# P_ytka_ESPv1.net
KiCad netlist of a schematic drawn in EAGLE
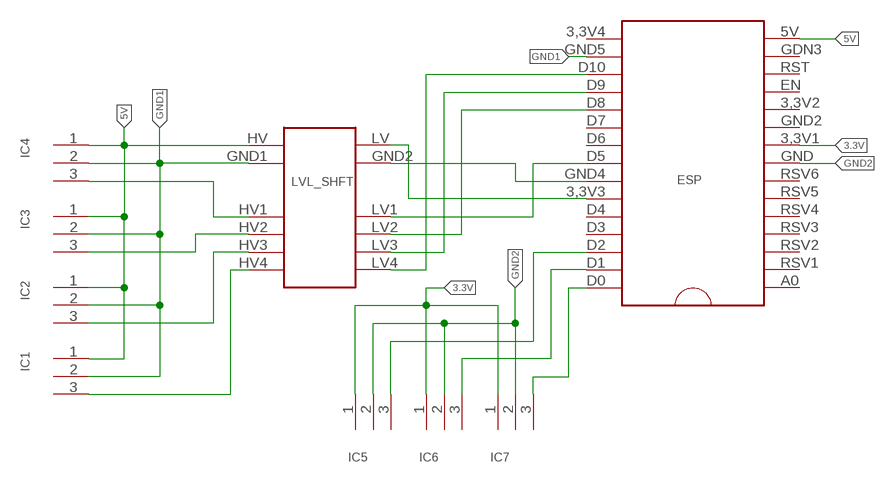
[diagram p0: schematic, sheet 1]

(export (version "E")
  (design (tool "Eeschema 10.0.6"))
  (components
    (comp (ref "ESP")
      (value "ESP8266_NODEMCUV2")
      (footprint "eagle-import:ESP8266_NODEMCV2")
      (libsource (lib "eagle-import") (part "ESP8266_NODEMCUV2"))
    )
    (comp (ref "IC1")
      (value "3,5MM_3PIN")
      (footprint "eagle-import:3,5MM_3PIN")
      (libsource (lib "eagle-import") (part "3,5MM_3PIN"))
    )
    (comp (ref "IC2")
      (value "3,5MM_3PIN")
      (footprint "eagle-import:3,5MM_3PIN")
      (libsource (lib "eagle-import") (part "3,5MM_3PIN"))
    )
    (comp (ref "IC3")
      (value "3,5MM_3PIN")
      (footprint "eagle-import:3,5MM_3PIN")
      (libsource (lib "eagle-import") (part "3,5MM_3PIN"))
    )
    (comp (ref "IC4")
      (value "3,5MM_3PIN")
      (footprint "eagle-import:3,5MM_3PIN")
      (libsource (lib "eagle-import") (part "3,5MM_3PIN"))
    )
    (comp (ref "IC5")
      (value "3,5MM_3PIN")
      (footprint "eagle-import:3,5MM_3PIN")
      (libsource (lib "eagle-import") (part "3,5MM_3PIN"))
    )
    (comp (ref "IC6")
      (value "3,5MM_3PIN")
      (footprint "eagle-import:3,5MM_3PIN")
      (libsource (lib "eagle-import") (part "3,5MM_3PIN"))
    )
    (comp (ref "IC7")
      (value "3,5MM_3PIN")
      (footprint "eagle-import:3,5MM_3PIN")
      (libsource (lib "eagle-import") (part "3,5MM_3PIN"))
    )
    (comp (ref "LVL_SHFT")
      (value "LVL_SHIFTER_4CH")
      (footprint "eagle-import:LVL_SHIFTER_4CH")
      (libsource (lib "eagle-import") (part "LVL_SHIFTER_4CH"))
    )
  )
  (nets
    (net (code "1") (name "3.3V") (class "Default")
      (node (ref "ESP") (pin "3,3V1") (pinfunction "P$9_3,3V1") (pintype "bidirectional"))
      (node (ref "IC5") (pin "1") (pinfunction "P$1_1") (pintype "bidirectional"))
      (node (ref "IC6") (pin "1") (pinfunction "P$1_1") (pintype "bidirectional"))
      (node (ref "IC7") (pin "1") (pinfunction "P$1_1") (pintype "bidirectional"))
    )
    (net (code "2") (name "5V") (class "Default")
      (node (ref "ESP") (pin "5V") (pinfunction "P$15_5V") (pintype "bidirectional"))
      (node (ref "IC1") (pin "1") (pinfunction "P$1_1") (pintype "bidirectional"))
      (node (ref "IC2") (pin "1") (pinfunction "P$1_1") (pintype "bidirectional"))
      (node (ref "IC3") (pin "1") (pinfunction "P$1_1") (pintype "bidirectional"))
      (node (ref "IC4") (pin "1") (pinfunction "P$1_1") (pintype "bidirectional"))
      (node (ref "LVL_SHFT") (pin "HV") (pinfunction "HV_HV") (pintype "bidirectional"))
    )
    (net (code "3") (name "GND1") (class "Default")
      (node (ref "ESP") (pin "GND5") (pinfunction "P$17_GND5") (pintype "bidirectional"))
      (node (ref "IC1") (pin "2") (pinfunction "P$2_2") (pintype "bidirectional"))
      (node (ref "IC2") (pin "2") (pinfunction "P$2_2") (pintype "bidirectional"))
      (node (ref "IC3") (pin "2") (pinfunction "P$2_2") (pintype "bidirectional"))
      (node (ref "IC4") (pin "2") (pinfunction "P$2_2") (pintype "bidirectional"))
      (node (ref "LVL_SHFT") (pin "GND1") (pinfunction "GND1_GND1") (pintype "bidirectional"))
    )
    (net (code "4") (name "GND2") (class "Default")
      (node (ref "ESP") (pin "GND") (pinfunction "P$8_GND") (pintype "bidirectional"))
      (node (ref "IC5") (pin "2") (pinfunction "P$2_2") (pintype "bidirectional"))
      (node (ref "IC6") (pin "2") (pinfunction "P$2_2") (pintype "bidirectional"))
      (node (ref "IC7") (pin "2") (pinfunction "P$2_2") (pintype "bidirectional"))
    )
    (net (code "5") (name "Net-(ESP-P$18)") (class "Default")
      (node (ref "ESP") (pin "D10") (pinfunction "P$18_D10") (pintype "bidirectional"))
      (node (ref "LVL_SHFT") (pin "LV4") (pinfunction "LV4_LV4") (pintype "bidirectional"))
    )
    (net (code "6") (name "Net-(ESP-P$19)") (class "Default")
      (node (ref "ESP") (pin "D9") (pinfunction "P$19_D9") (pintype "bidirectional"))
      (node (ref "LVL_SHFT") (pin "LV3") (pinfunction "LV3_LV3") (pintype "bidirectional"))
    )
    (net (code "7") (name "Net-(ESP-P$20)") (class "Default")
      (node (ref "ESP") (pin "D8") (pinfunction "P$20_D8") (pintype "bidirectional"))
      (node (ref "LVL_SHFT") (pin "LV2") (pinfunction "LV2_LV2") (pintype "bidirectional"))
    )
    (net (code "8") (name "Net-(ESP-P$23)") (class "Default")
      (node (ref "ESP") (pin "D5") (pinfunction "P$23_D5") (pintype "bidirectional"))
      (node (ref "LVL_SHFT") (pin "LV1") (pinfunction "LV1_LV1") (pintype "bidirectional"))
    )
    (net (code "9") (name "Net-(ESP-P$24)") (class "Default")
      (node (ref "ESP") (pin "GND4") (pinfunction "P$24_GND4") (pintype "bidirectional"))
      (node (ref "LVL_SHFT") (pin "GND2") (pinfunction "GND2_GND2") (pintype "bidirectional"))
    )
    (net (code "10") (name "Net-(ESP-P$25)") (class "Default")
      (node (ref "ESP") (pin "3,3V3") (pinfunction "P$25_3,3V3") (pintype "bidirectional"))
      (node (ref "LVL_SHFT") (pin "LV") (pinfunction "LV_LV") (pintype "bidirectional"))
    )
    (net (code "11") (name "Net-(ESP-P$28)") (class "Default")
      (node (ref "ESP") (pin "D2") (pinfunction "P$28_D2") (pintype "bidirectional"))
      (node (ref "IC5") (pin "3") (pinfunction "P$3_3") (pintype "bidirectional"))
    )
    (net (code "12") (name "Net-(ESP-P$29)") (class "Default")
      (node (ref "ESP") (pin "D1") (pinfunction "P$29_D1") (pintype "bidirectional"))
      (node (ref "IC6") (pin "3") (pinfunction "P$3_3") (pintype "bidirectional"))
    )
    (net (code "13") (name "Net-(ESP-P$30)") (class "Default")
      (node (ref "ESP") (pin "D0") (pinfunction "P$30_D0") (pintype "bidirectional"))
      (node (ref "IC7") (pin "3") (pinfunction "P$3_3") (pintype "bidirectional"))
    )
    (net (code "14") (name "Net-(IC1-P$3)") (class "Default")
      (node (ref "IC1") (pin "3") (pinfunction "P$3_3") (pintype "bidirectional"))
      (node (ref "LVL_SHFT") (pin "HV4") (pinfunction "HV4_HV4") (pintype "bidirectional"))
    )
    (net (code "15") (name "Net-(IC2-P$3)") (class "Default")
      (node (ref "IC2") (pin "3") (pinfunction "P$3_3") (pintype "bidirectional"))
      (node (ref "LVL_SHFT") (pin "HV3") (pinfunction "HV3_HV3") (pintype "bidirectional"))
    )
    (net (code "16") (name "Net-(IC3-P$3)") (class "Default")
      (node (ref "IC3") (pin "3") (pinfunction "P$3_3") (pintype "bidirectional"))
      (node (ref "LVL_SHFT") (pin "HV2") (pinfunction "HV2_HV2") (pintype "bidirectional"))
    )
    (net (code "17") (name "Net-(IC4-P$3)") (class "Default")
      (node (ref "IC4") (pin "3") (pinfunction "P$3_3") (pintype "bidirectional"))
      (node (ref "LVL_SHFT") (pin "HV1") (pinfunction "HV1_HV1") (pintype "bidirectional"))
    )
    (net (code "18") (name "unconnected-(ESP-P$1-PadA0)") (class "Default")
      (node (ref "ESP") (pin "A0") (pinfunction "P$1_A0") (pintype "bidirectional"))
    )
    (net (code "19") (name "unconnected-(ESP-P$2-PadRSV1)") (class "Default")
      (node (ref "ESP") (pin "RSV1") (pinfunction "P$2_RSV1") (pintype "bidirectional"))
    )
    (net (code "20") (name "unconnected-(ESP-P$3-PadRSV2)") (class "Default")
      (node (ref "ESP") (pin "RSV2") (pinfunction "P$3_RSV2") (pintype "bidirectional"))
    )
    (net (code "21") (name "unconnected-(ESP-P$4-PadRSV3)") (class "Default")
      (node (ref "ESP") (pin "RSV3") (pinfunction "P$4_RSV3") (pintype "bidirectional"))
    )
    (net (code "22") (name "unconnected-(ESP-P$5-PadRSV4)") (class "Default")
      (node (ref "ESP") (pin "RSV4") (pinfunction "P$5_RSV4") (pintype "bidirectional"))
    )
    (net (code "23") (name "unconnected-(ESP-P$6-PadRSV5)") (class "Default")
      (node (ref "ESP") (pin "RSV5") (pinfunction "P$6_RSV5") (pintype "bidirectional"))
    )
    (net (code "24") (name "unconnected-(ESP-P$7-PadRSV6)") (class "Default")
      (node (ref "ESP") (pin "RSV6") (pinfunction "P$7_RSV6") (pintype "bidirectional"))
    )
    (net (code "25") (name "unconnected-(ESP-P$10-PadGND2)") (class "Default")
      (node (ref "ESP") (pin "GND2") (pinfunction "P$10_GND2") (pintype "bidirectional"))
    )
    (net (code "26") (name "unconnected-(ESP-P$11-Pad3,3V2)") (class "Default")
      (node (ref "ESP") (pin "3,3V2") (pinfunction "P$11_3,3V2") (pintype "bidirectional"))
    )
    (net (code "27") (name "unconnected-(ESP-P$12-PadEN)") (class "Default")
      (node (ref "ESP") (pin "EN") (pinfunction "P$12_EN") (pintype "bidirectional"))
    )
    (net (code "28") (name "unconnected-(ESP-P$13-PadRST)") (class "Default")
      (node (ref "ESP") (pin "RST") (pinfunction "P$13_RST") (pintype "bidirectional"))
    )
    (net (code "29") (name "unconnected-(ESP-P$14-PadGDN3)") (class "Default")
      (node (ref "ESP") (pin "GDN3") (pinfunction "P$14_GDN3") (pintype "bidirectional"))
    )
    (net (code "30") (name "unconnected-(ESP-P$16-Pad3,3V4)") (class "Default")
      (node (ref "ESP") (pin "3,3V4") (pinfunction "P$16_3,3V4") (pintype "bidirectional"))
    )
    (net (code "31") (name "unconnected-(ESP-P$21-PadD7)") (class "Default")
      (node (ref "ESP") (pin "D7") (pinfunction "P$21_D7") (pintype "bidirectional"))
    )
    (net (code "32") (name "unconnected-(ESP-P$22-PadD6)") (class "Default")
      (node (ref "ESP") (pin "D6") (pinfunction "P$22_D6") (pintype "bidirectional"))
    )
    (net (code "33") (name "unconnected-(ESP-P$26-PadD4)") (class "Default")
      (node (ref "ESP") (pin "D4") (pinfunction "P$26_D4") (pintype "bidirectional"))
    )
    (net (code "34") (name "unconnected-(ESP-P$27-PadD3)") (class "Default")
      (node (ref "ESP") (pin "D3") (pinfunction "P$27_D3") (pintype "bidirectional"))
    )
  )
)
